# Sheet1.net
KiCad netlist of a schematic drawn in Altium Designer
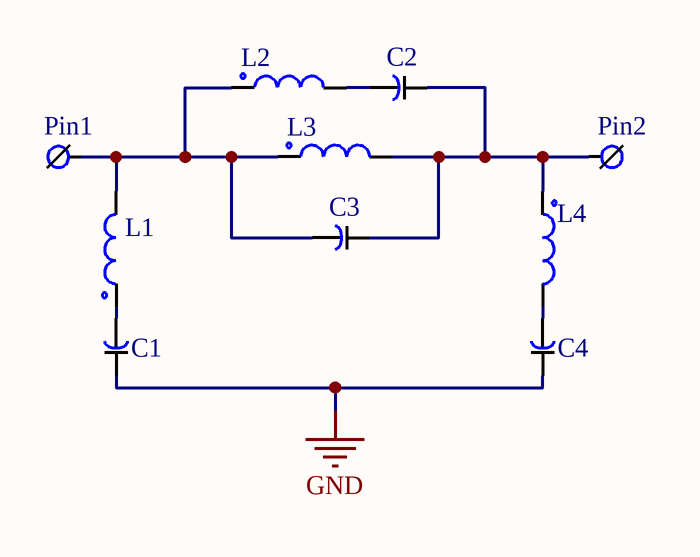
[diagram p0: Sheet1.SchDoc]

(export (version "E")
  (design (tool "Eeschema 10.0.6"))
  (components
    (comp (ref "C1") (value "C1,C4") (footprint "C1,C4(0805)") (libsource (lib "Schlib") (part "C1,C4")))
    (comp (ref "C2") (value "C2") (footprint "C2(0603)") (libsource (lib "Schlib") (part "C2")))
    (comp (ref "C3") (value "C3") (footprint "C3(1206)") (libsource (lib "Schlib") (part "C3")))
    (comp (ref "C4") (value "C1,C4") (footprint "C1,C4(0805)") (libsource (lib "Schlib") (part "C1,C4")))
    (comp (ref "L1") (value "L1,L4,L3") (footprint "L1,L4,L3") (libsource (lib "Schlib") (part "L1,L4,L3")))
    (comp (ref "L2") (value "L2") (footprint "L2") (libsource (lib "Schlib") (part "L2")))
    (comp (ref "L3") (value "L1,L4,L3") (footprint "L1,L4,L3") (libsource (lib "Schlib") (part "L1,L4,L3")))
    (comp (ref "L4") (value "L1,L4,L3") (footprint "L1,L4,L3") (libsource (lib "Schlib") (part "L1,L4,L3")))
    (comp (ref "Pin1") (value "Comment") (footprint "Pin") (libsource (lib "Schlib") (part "Pin")))
    (comp (ref "Pin2") (value "Pin") (footprint "Pin") (libsource (lib "Schlib") (part "Pin")))
  )
  (nets
    (net (code "1") (name "GND") (class "Default")
      (node (ref "C1") (pin "2") (pinfunction "2_2") (pintype "passive"))
      (node (ref "C4") (pin "2") (pinfunction "2_2") (pintype "passive"))
    )
    (net (code "2") (name "Net-(C1-Pad1)") (class "Default")
      (node (ref "C1") (pin "1") (pinfunction "1_1") (pintype "passive"))
      (node (ref "L1") (pin "1") (pinfunction "1_1") (pintype "passive"))
    )
    (net (code "3") (name "Net-(C2-Pad1)") (class "Default")
      (node (ref "C2") (pin "1") (pinfunction "1_1") (pintype "passive"))
      (node (ref "L2") (pin "2") (pinfunction "2_2") (pintype "passive"))
    )
    (net (code "4") (name "Net-(C4-Pad1)") (class "Default")
      (node (ref "C4") (pin "1") (pinfunction "1_1") (pintype "passive"))
      (node (ref "L4") (pin "2") (pinfunction "2_2") (pintype "passive"))
    )
    (net (code "5") (name "Net-(Pin1-4)") (class "Default")
      (node (ref "C3") (pin "1") (pinfunction "1_1") (pintype "passive"))
      (node (ref "L1") (pin "2") (pinfunction "2_2") (pintype "passive"))
      (node (ref "L2") (pin "1") (pinfunction "1_1") (pintype "passive"))
      (node (ref "L3") (pin "1") (pinfunction "1_1") (pintype "passive"))
      (node (ref "Pin1") (pin "1") (pinfunction "4_1") (pintype "passive"))
    )
    (net (code "6") (name "Net-(Pin2-4)") (class "Default")
      (node (ref "C2") (pin "2") (pinfunction "2_2") (pintype "passive"))
      (node (ref "C3") (pin "2") (pinfunction "2_2") (pintype "passive"))
      (node (ref "L3") (pin "2") (pinfunction "2_2") (pintype "passive"))
      (node (ref "L4") (pin "1") (pinfunction "1_1") (pintype "passive"))
      (node (ref "Pin2") (pin "1") (pinfunction "4_1") (pintype "passive"))
    )
  )
)
